# power.net
KiCad netlist of a schematic drawn in Altium Designer
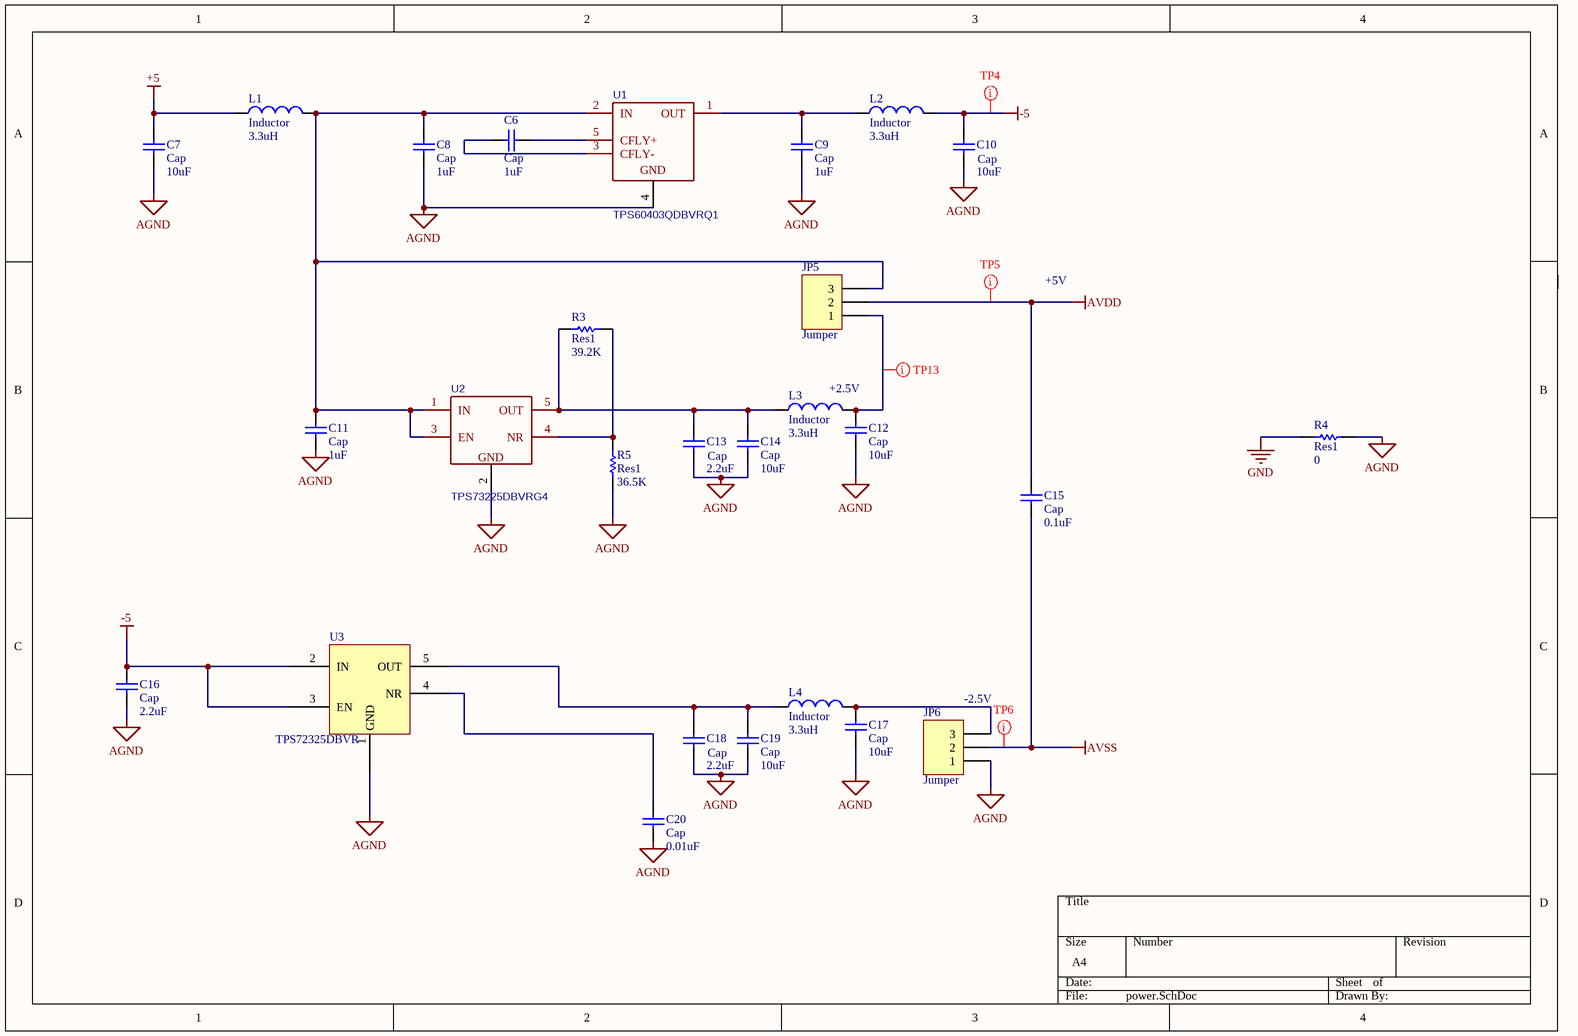
[diagram p0: power.SchDoc]

(export (version "E")
  (design (tool "Eeschema 10.0.6"))
  (components
    (comp (ref "C6")
      (value "Cap")
      (footprint "1608[0603]")
      (description "Capacitor")
      (fields (field (name "ALTIUM_VALUE") "1uF") (field (name "PUBLISHER") "Altium Limited"))
      (libsource (lib "Miscellaneous Devices") (part "Cap"))
    )
    (comp (ref "C7")
      (value "Cap")
      (footprint "6-0805_N")
      (description "Capacitor")
      (fields (field (name "ALTIUM_VALUE") "10uF") (field (name "PUBLISHER") "Altium Limited"))
      (libsource (lib "Miscellaneous Devices") (part "Cap"))
    )
    (comp (ref "C8")
      (value "Cap")
      (footprint "1608[0603]")
      (description "Capacitor")
      (fields (field (name "ALTIUM_VALUE") "1uF") (field (name "PUBLISHER") "Altium Limited"))
      (libsource (lib "Miscellaneous Devices") (part "Cap"))
    )
    (comp (ref "C9")
      (value "Cap")
      (footprint "1608[0603]")
      (description "Capacitor")
      (fields (field (name "ALTIUM_VALUE") "1uF") (field (name "PUBLISHER") "Altium Limited"))
      (libsource (lib "Miscellaneous Devices") (part "Cap"))
    )
    (comp (ref "C10")
      (value "Cap")
      (footprint "6-0805_N")
      (description "Capacitor")
      (fields (field (name "ALTIUM_VALUE") "10uF") (field (name "PUBLISHER") "Altium Limited"))
      (libsource (lib "Miscellaneous Devices") (part "Cap"))
    )
    (comp (ref "C11")
      (value "Cap")
      (footprint "1608[0603]")
      (description "Capacitor")
      (fields (field (name "ALTIUM_VALUE") "1uF") (field (name "PUBLISHER") "Altium Limited"))
      (libsource (lib "Miscellaneous Devices") (part "Cap"))
    )
    (comp (ref "C12")
      (value "Cap")
      (footprint "6-0805_N")
      (description "Capacitor")
      (fields (field (name "ALTIUM_VALUE") "10uF") (field (name "PUBLISHER") "Altium Limited"))
      (libsource (lib "Miscellaneous Devices") (part "Cap"))
    )
    (comp (ref "C13")
      (value "Cap")
      (footprint "1608[0603]")
      (description "Capacitor")
      (fields (field (name "ALTIUM_VALUE") "2.2uF") (field (name "PUBLISHER") "Altium Limited"))
      (libsource (lib "Miscellaneous Devices") (part "Cap"))
    )
    (comp (ref "C14")
      (value "Cap")
      (footprint "6-0805_N")
      (description "Capacitor")
      (fields (field (name "ALTIUM_VALUE") "10uF") (field (name "PUBLISHER") "Altium Limited"))
      (libsource (lib "Miscellaneous Devices") (part "Cap"))
    )
    (comp (ref "C15")
      (value "Cap")
      (footprint "1608[0603]")
      (description "Capacitor")
      (fields (field (name "ALTIUM_VALUE") "0.1uF") (field (name "PUBLISHER") "Altium Limited"))
      (libsource (lib "Miscellaneous Devices") (part "Cap"))
    )
    (comp (ref "C16")
      (value "Cap")
      (footprint "1608[0603]")
      (description "Capacitor")
      (fields (field (name "ALTIUM_VALUE") "2.2uF") (field (name "PUBLISHER") "Altium Limited"))
      (libsource (lib "Miscellaneous Devices") (part "Cap"))
    )
    (comp (ref "C17")
      (value "Cap")
      (footprint "6-0805_N")
      (description "Capacitor")
      (fields (field (name "ALTIUM_VALUE") "10uF") (field (name "PUBLISHER") "Altium Limited"))
      (libsource (lib "Miscellaneous Devices") (part "Cap"))
    )
    (comp (ref "C18")
      (value "Cap")
      (footprint "1608[0603]")
      (description "Capacitor")
      (fields (field (name "ALTIUM_VALUE") "2.2uF") (field (name "PUBLISHER") "Altium Limited"))
      (libsource (lib "Miscellaneous Devices") (part "Cap"))
    )
    (comp (ref "C19")
      (value "Cap")
      (footprint "6-0805_N")
      (description "Capacitor")
      (fields (field (name "ALTIUM_VALUE") "10uF") (field (name "PUBLISHER") "Altium Limited"))
      (libsource (lib "Miscellaneous Devices") (part "Cap"))
    )
    (comp (ref "C20")
      (value "Cap")
      (footprint "1608[0603]")
      (description "Capacitor")
      (fields (field (name "ALTIUM_VALUE") "0.01uF") (field (name "PUBLISHER") "Altium Limited"))
      (libsource (lib "Miscellaneous Devices") (part "Cap"))
    )
    (comp (ref "JP5")
      (value "Jumper")
      (footprint "HDR1X3")
      (description "Header, 3-Pin")
      (fields (field (name "PUBLISHER") "Altium Limited"))
      (libsource (lib "Miscellaneous Connectors") (part "Header 3"))
    )
    (comp (ref "JP6")
      (value "Jumper")
      (footprint "HDR1X3")
      (description "Header, 3-Pin")
      (fields (field (name "PUBLISHER") "Altium Limited"))
      (libsource (lib "Miscellaneous Connectors") (part "Header 3"))
    )
    (comp (ref "L1")
      (value "Inductor")
      (footprint "6-0805_M")
      (fields (field (name "ALTIUM_VALUE") "3.3uH") (field (name "PUBLISHER") "Altium Limited"))
      (libsource (lib "Miscellaneous Devices") (part "Inductor"))
    )
    (comp (ref "L2")
      (value "Inductor")
      (footprint "6-0805_M")
      (fields (field (name "ALTIUM_VALUE") "3.3uH") (field (name "PUBLISHER") "Altium Limited"))
      (libsource (lib "Miscellaneous Devices") (part "Inductor"))
    )
    (comp (ref "L3")
      (value "Inductor")
      (footprint "6-0805_M")
      (fields (field (name "ALTIUM_VALUE") "3.3uH") (field (name "PUBLISHER") "Altium Limited"))
      (libsource (lib "Miscellaneous Devices") (part "Inductor"))
    )
    (comp (ref "L4")
      (value "Inductor")
      (footprint "6-0805_M")
      (fields (field (name "ALTIUM_VALUE") "3.3uH") (field (name "PUBLISHER") "Altium Limited"))
      (libsource (lib "Miscellaneous Devices") (part "Inductor"))
    )
    (comp (ref "R3")
      (value "Res1")
      (footprint "1608[0603]")
      (description "Resistor")
      (fields (field (name "ALTIUM_VALUE") "39.2K") (field (name "PUBLISHER") "Altium Limited"))
      (libsource (lib "Miscellaneous Devices") (part "Res1"))
    )
    (comp (ref "R4")
      (value "Res1")
      (footprint "1608[0603]")
      (description "Resistor")
      (fields (field (name "ALTIUM_VALUE") "0") (field (name "PUBLISHER") "Altium Limited"))
      (libsource (lib "Miscellaneous Devices") (part "Res1"))
    )
    (comp (ref "R5")
      (value "Res1")
      (footprint "1608[0603]")
      (description "Resistor")
      (fields (field (name "ALTIUM_VALUE") "36.5K") (field (name "PUBLISHER") "Altium Limited"))
      (libsource (lib "Miscellaneous Devices") (part "Res1"))
    )
    (comp (ref "U1")
      (value "TPS60403QDBVRQ1")
      (footprint "DBV5")
      (fields (field (name "BOM_SUPPLIER PART") "C130215") (field (name "CONTRIBUTOR") "LCSC"))
      (libsource (lib "PCB_Project_TEMP") (part "TPS60403QDBVRQ1"))
    )
    (comp (ref "U2")
      (value "TPS73225DBVRG4")
      (footprint "myPCBlibrary:SOT23-5")
      (libsource (lib "PCB_Project_TEMP") (part "TPS73225DBVRG4"))
    )
    (comp (ref "U3")
      (value "TPS72325DBVR")
      (footprint "DBV0005A")
      (libsource (lib "Schlib1") (part "TPS72325DBVR"))
    )
  )
  (nets
    (net (code "1") (name "+5") (class "Default")
      (node (ref "C7") (pin "2") (pinfunction "2_2") (pintype "passive"))
      (node (ref "L1") (pin "1") (pinfunction "1_1") (pintype "passive"))
    )
    (net (code "2") (name "-5") (class "Default")
      (node (ref "C10") (pin "2") (pinfunction "2_2") (pintype "passive"))
      (node (ref "C16") (pin "2") (pinfunction "2_2") (pintype "passive"))
      (node (ref "L2") (pin "2") (pinfunction "2_2") (pintype "passive"))
      (node (ref "U3") (pin "2") (pinfunction "IN_2") (pintype "passive"))
      (node (ref "U3") (pin "3") (pinfunction "EN_3") (pintype "passive"))
    )
    (net (code "3") (name "AGND") (class "Default")
      (node (ref "C10") (pin "1") (pinfunction "1_1") (pintype "passive"))
      (node (ref "C11") (pin "1") (pinfunction "1_1") (pintype "passive"))
      (node (ref "C12") (pin "1") (pinfunction "1_1") (pintype "passive"))
      (node (ref "C13") (pin "1") (pinfunction "1_1") (pintype "passive"))
      (node (ref "C14") (pin "1") (pinfunction "1_1") (pintype "passive"))
      (node (ref "C16") (pin "1") (pinfunction "1_1") (pintype "passive"))
      (node (ref "C17") (pin "1") (pinfunction "1_1") (pintype "passive"))
      (node (ref "C18") (pin "1") (pinfunction "1_1") (pintype "passive"))
      (node (ref "C19") (pin "1") (pinfunction "1_1") (pintype "passive"))
      (node (ref "C20") (pin "1") (pinfunction "1_1") (pintype "passive"))
      (node (ref "C7") (pin "1") (pinfunction "1_1") (pintype "passive"))
      (node (ref "C8") (pin "1") (pinfunction "1_1") (pintype "passive"))
      (node (ref "C9") (pin "1") (pinfunction "1_1") (pintype "passive"))
      (node (ref "JP6") (pin "1") (pinfunction "1_1") (pintype "passive"))
      (node (ref "R4") (pin "1") (pinfunction "1_1") (pintype "passive"))
      (node (ref "R5") (pin "1") (pinfunction "1_1") (pintype "passive"))
      (node (ref "U1") (pin "4") (pinfunction "GND_4") (pintype "passive"))
      (node (ref "U2") (pin "2") (pinfunction "GND_2") (pintype "passive"))
      (node (ref "U3") (pin "1") (pinfunction "GND_1") (pintype "passive"))
    )
    (net (code "4") (name "AVDD") (class "Default")
      (node (ref "C15") (pin "2") (pinfunction "2_2") (pintype "passive"))
      (node (ref "JP5") (pin "2") (pinfunction "2_2") (pintype "passive"))
    )
    (net (code "5") (name "AVSS") (class "Default")
      (node (ref "C15") (pin "1") (pinfunction "1_1") (pintype "passive"))
      (node (ref "JP6") (pin "2") (pinfunction "2_2") (pintype "passive"))
    )
    (net (code "6") (name "GND") (class "Default")
      (node (ref "R4") (pin "2") (pinfunction "2_2") (pintype "passive"))
    )
    (net (code "7") (name "Net-(C12-Pad2)") (class "Default")
      (node (ref "C12") (pin "2") (pinfunction "2_2") (pintype "passive"))
      (node (ref "JP5") (pin "1") (pinfunction "1_1") (pintype "passive"))
      (node (ref "L3") (pin "2") (pinfunction "2_2") (pintype "passive"))
    )
    (net (code "8") (name "Net-(C17-Pad2)") (class "Default")
      (node (ref "C17") (pin "2") (pinfunction "2_2") (pintype "passive"))
      (node (ref "JP6") (pin "3") (pinfunction "3_3") (pintype "passive"))
      (node (ref "L4") (pin "2") (pinfunction "2_2") (pintype "passive"))
    )
    (net (code "9") (name "Net-(U1-CFLY+)") (class "Default")
      (node (ref "C6") (pin "1") (pinfunction "1_1") (pintype "passive"))
      (node (ref "U1") (pin "5") (pinfunction "CFLY+_5") (pintype "passive"))
    )
    (net (code "10") (name "Net-(U1-CFLY-)") (class "Default")
      (node (ref "C6") (pin "2") (pinfunction "2_2") (pintype "passive"))
      (node (ref "U1") (pin "3") (pinfunction "CFLY-_3") (pintype "passive"))
    )
    (net (code "11") (name "Net-(U1-IN)") (class "Default")
      (node (ref "C11") (pin "2") (pinfunction "2_2") (pintype "passive"))
      (node (ref "C8") (pin "2") (pinfunction "2_2") (pintype "passive"))
      (node (ref "JP5") (pin "3") (pinfunction "3_3") (pintype "passive"))
      (node (ref "L1") (pin "2") (pinfunction "2_2") (pintype "passive"))
      (node (ref "U1") (pin "2") (pinfunction "IN_2") (pintype "passive"))
      (node (ref "U2") (pin "1") (pinfunction "IN_1") (pintype "passive"))
      (node (ref "U2") (pin "3") (pinfunction "EN_3") (pintype "passive"))
    )
    (net (code "12") (name "Net-(U1-OUT)") (class "Default")
      (node (ref "C9") (pin "2") (pinfunction "2_2") (pintype "passive"))
      (node (ref "L2") (pin "1") (pinfunction "1_1") (pintype "passive"))
      (node (ref "U1") (pin "1") (pinfunction "OUT_1") (pintype "passive"))
    )
    (net (code "13") (name "Net-(U2-NR)") (class "Default")
      (node (ref "R3") (pin "2") (pinfunction "2_2") (pintype "passive"))
      (node (ref "R5") (pin "2") (pinfunction "2_2") (pintype "passive"))
      (node (ref "U2") (pin "4") (pinfunction "NR_4") (pintype "passive"))
    )
    (net (code "14") (name "Net-(U2-OUT)") (class "Default")
      (node (ref "C13") (pin "2") (pinfunction "2_2") (pintype "passive"))
      (node (ref "C14") (pin "2") (pinfunction "2_2") (pintype "passive"))
      (node (ref "L3") (pin "1") (pinfunction "1_1") (pintype "passive"))
      (node (ref "R3") (pin "1") (pinfunction "1_1") (pintype "passive"))
      (node (ref "U2") (pin "5") (pinfunction "OUT_5") (pintype "passive"))
    )
    (net (code "15") (name "Net-(U3-NR)") (class "Default")
      (node (ref "C20") (pin "2") (pinfunction "2_2") (pintype "passive"))
      (node (ref "U3") (pin "4") (pinfunction "NR_4") (pintype "passive"))
    )
    (net (code "16") (name "Net-(U3-OUT)") (class "Default")
      (node (ref "C18") (pin "2") (pinfunction "2_2") (pintype "passive"))
      (node (ref "C19") (pin "2") (pinfunction "2_2") (pintype "passive"))
      (node (ref "L4") (pin "1") (pinfunction "1_1") (pintype "passive"))
      (node (ref "U3") (pin "5") (pinfunction "OUT_5") (pintype "passive"))
    )
  )
)
